# MotorDriver.net
KiCad netlist of a schematic drawn in EAGLE
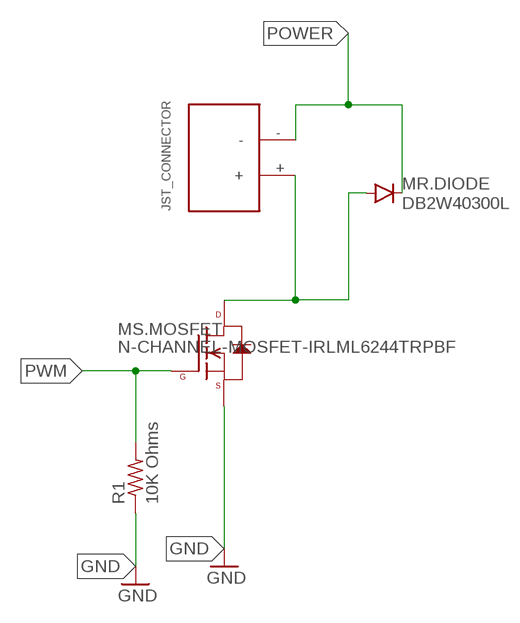
[diagram p0: schematic, sheet 1]

(export (version "E")
  (design (tool "Eeschema 10.0.6"))
  (components
    (comp (ref "MOTOR")
      (value "JST_CONNECTOR_FEMALE")
      (footprint "eagle-import:JST_CONNECTOR_FEMALE")
      (libsource (lib "eagle-import") (part "JST_CONNECTOR_FEMALE"))
    )
    (comp (ref "MR.DIODE")
      (value "DB2W40300L")
      (footprint "eagle-import:MINI2-F3-B")
      (libsource (lib "eagle-import") (part "DB2W40300L"))
    )
    (comp (ref "MS.MOSFET")
      (value "N-CHANNEL-MOSFET-IRLML6244TRPBF")
      (footprint "eagle-import:SOT23-3")
      (libsource (lib "eagle-import") (part "N-CHANNEL-MOSFET-IRLML6244TRPBF"))
    )
    (comp (ref "R1")
      (value "10K Ohms")
      (footprint "eagle-import:0204_5")
      (libsource (lib "eagle-import") (part "R-US_0204/5"))
    )
  )
  (nets
    (net (code "1") (name "GND") (class "Default")
      (node (ref "MS.MOSFET") (pin "2") (pinfunction "S_2") (pintype "passive"))
      (node (ref "R1") (pin "1") (pinfunction "1_1") (pintype "passive"))
    )
    (net (code "2") (name "Net-(MR.DIODE-PPIN)") (class "Default")
      (node (ref "MOTOR") (pin "+") (pinfunction "+_+") (pintype "bidirectional"))
      (node (ref "MR.DIODE") (pin "POS") (pinfunction "PPIN_POS") (pintype "passive"))
      (node (ref "MS.MOSFET") (pin "3") (pinfunction "D_3") (pintype "passive"))
    )
    (net (code "3") (name "POWER") (class "Default")
      (node (ref "MOTOR") (pin "-") (pinfunction "-_-") (pintype "bidirectional"))
      (node (ref "MR.DIODE") (pin "NEG") (pinfunction "GPIN_NEG") (pintype "passive"))
    )
    (net (code "4") (name "PWM") (class "Default")
      (node (ref "MS.MOSFET") (pin "1") (pinfunction "G_1") (pintype "passive"))
      (node (ref "R1") (pin "2") (pinfunction "2_2") (pintype "passive"))
    )
  )
)
